# Com_Canbus.net
KiCad netlist of a schematic drawn in Altium Designer
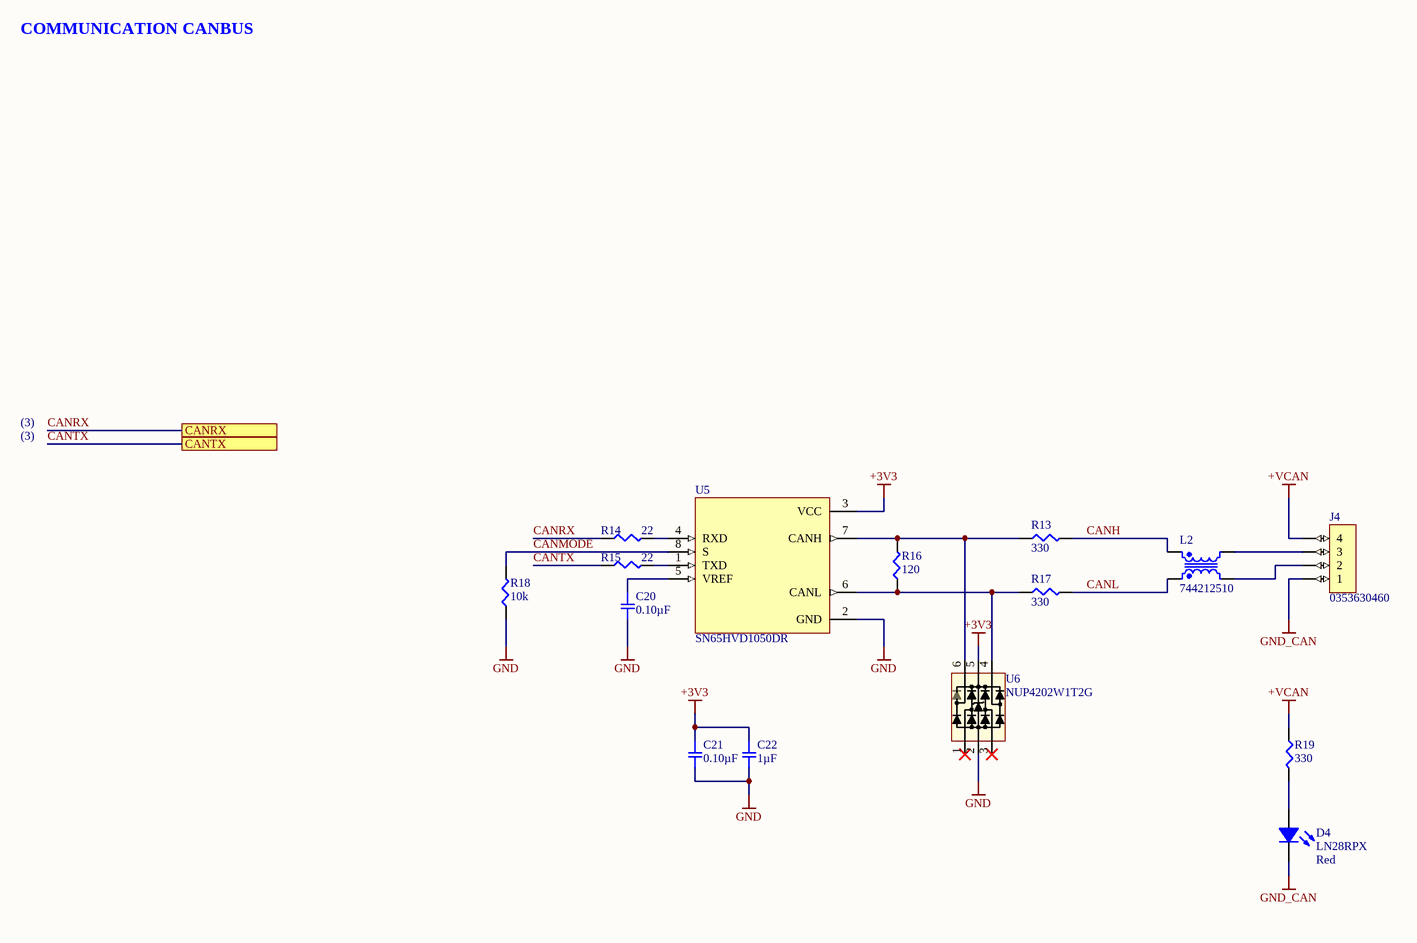
[diagram p0: Com_Canbus.SchDoc]

(export (version "E")
  (design (tool "Eeschema 10.0.6"))
  (components
    (comp (ref "C20")
      (value "0.10µF")
      (footprint "SMD-0603C")
      (description "CAP CER 0.1UF 50V X7R 0603")
      (fields
        (field (name "DIGI-KEY PART NUMBER") "490-5798-1-ND")
        (field (name "PART NUMBER") "GCJ188R71H104KA12D")
      )
      (libsource (lib "capacitor_murata_0603") (part "GCJ188R71H104KA12D"))
    )
    (comp (ref "C21")
      (value "0.10µF")
      (footprint "SMD-0603C")
      (description "CAP CER 0.1UF 50V X7R 0603")
      (fields
        (field (name "DIGI-KEY PART NUMBER") "490-5798-1-ND")
        (field (name "PART NUMBER") "GCJ188R71H104KA12D")
      )
      (libsource (lib "capacitor_murata_0603") (part "GCJ188R71H104KA12D"))
    )
    (comp (ref "C22")
      (value "1µF")
      (footprint "SMD-0603C")
      (description "CAP CER 1UF 16V X7R 0603")
      (fields
        (field (name "DIGI-KEY PART NUMBER") "490-5241-1-ND")
        (field (name "PART NUMBER") "GCM188R71C105KA64D")
      )
      (libsource (lib "capacitor_murata_0603") (part "GCM188R71C105KA64D"))
    )
    (comp (ref "D4")
      (value "LN28RPX")
      (footprint "Led-3mm-Red-h7")
      (description "LED RED DIFF 3MM ROUND T/H")
      (fields
        (field (name "MANUFACTURER") "Panasonic Electronic Components")
        (field (name "LENS COLOR") "Red")
      )
      (libsource (lib "Altium_Lib") (part "LED_RED__LN28RPX"))
    )
    (comp (ref "J4")
      (value "0353630460")
      (footprint "CONN_4_POS__0353630460")
      (description "CONN HEADER 4POS 2MM R/A TIN")
      (fields (field (name "MANUFACTURER") "Molex Connector Corporation"))
      (libsource (lib "Altium_Lib") (part "CONN_4_POS__0353630460"))
    )
    (comp (ref "L2")
      (value "744212510")
      (footprint "CM_6.50mm x 3.60mm")
      (description "Common Mode Filters / Chokes WE-SL1 SMD Ln Filter 2x51uH 300ohm")
      (fields (field (name "MANUFACTURER") "Wurth Electronics") (field (name "TOLERANCE") "50%"))
      (libsource (lib "Altium_Lib") (part "CM__744212510"))
    )
    (comp (ref "R13")
      (value "330")
      (footprint "SMD-0603-RES")
      (description "RES SMD 330 OHM 1% 1/10W 0603")
      (fields (field (name "PART NUMBER") "ERJ-3EKF3300V") (field (name "DIGI-KEY PART NUMBER") "P330HCT-ND"))
      (libsource (lib "Panasonic_ERJ_0603") (part "ERJ-3EKF3300V"))
    )
    (comp (ref "R14")
      (value "22")
      (footprint "SMD-0603-RES")
      (description "RES SMD 22 OHM 1% 1/10W 0603")
      (fields
        (field (name "PART NUMBER") "ERJ-3EKF22R0V")
        (field (name "DIGI-KEY PART NUMBER") "P22.0HCT-ND")
      )
      (libsource (lib "Panasonic_ERJ_0603") (part "ERJ-3EKF22R0V"))
    )
    (comp (ref "R15")
      (value "22")
      (footprint "SMD-0603-RES")
      (description "RES SMD 22 OHM 1% 1/10W 0603")
      (fields
        (field (name "PART NUMBER") "ERJ-3EKF22R0V")
        (field (name "DIGI-KEY PART NUMBER") "P22.0HCT-ND")
      )
      (libsource (lib "Panasonic_ERJ_0603") (part "ERJ-3EKF22R0V"))
    )
    (comp (ref "R16")
      (value "120")
      (footprint "SMD-0603-RES")
      (description "RES SMD 120 OHM 1% 1/10W 0603")
      (fields (field (name "PART NUMBER") "ERJ-3EKF1200V") (field (name "DIGI-KEY PART NUMBER") "P120HCT-ND"))
      (libsource (lib "Panasonic_ERJ_0603") (part "ERJ-3EKF1200V"))
    )
    (comp (ref "R17")
      (value "330")
      (footprint "SMD-0603-RES")
      (description "RES SMD 330 OHM 1% 1/10W 0603")
      (fields (field (name "PART NUMBER") "ERJ-3EKF3300V") (field (name "DIGI-KEY PART NUMBER") "P330HCT-ND"))
      (libsource (lib "Panasonic_ERJ_0603") (part "ERJ-3EKF3300V"))
    )
    (comp (ref "R18")
      (value "10k")
      (footprint "SMD-0603-RES")
      (description "RES SMD 10K OHM 1% 1/10W 0603")
      (fields
        (field (name "PART NUMBER") "ERJ-3EKF1002V")
        (field (name "DIGI-KEY PART NUMBER") "P10.0KHCT-ND")
      )
      (libsource (lib "Panasonic_ERJ_0603") (part "ERJ-3EKF1002V"))
    )
    (comp (ref "R19")
      (value "330")
      (footprint "SMD-0603-RES")
      (description "RES SMD 330 OHM 1% 1/10W 0603")
      (fields (field (name "PART NUMBER") "ERJ-3EKF3300V") (field (name "DIGI-KEY PART NUMBER") "P330HCT-ND"))
      (libsource (lib "Panasonic_ERJ_0603") (part "ERJ-3EKF3300V"))
    )
    (comp (ref "U5")
      (value "SN65HVD1050DR")
      (footprint "SOIC-8_L")
      (description "High-Speed CAN Transceiver with Silent Mode 8-SOIC -40 to 125")
      (fields (field (name "DIGI-KEY_PART_NUMBER") "296-26335-1-ND") (field (name "MF") "Texas Instruments"))
      (libsource (lib "Altium_Lib") (part "SN65HVD1050DR"))
    )
    (comp (ref "U6")
      (value "NUP4202W1T2G")
      (footprint "SOT-363")
      (description "TVS DIODE 5VWM 14.5VC SOT363")
      (fields (field (name "MANUFACTURER") "ON Semiconductor"))
      (libsource (lib "Altium_Lib") (part "NUP4202W1T2G"))
    )
  )
  (nets
    (net (code "1") (name "+3V3") (class "Default")
      (node (ref "C21") (pin "1") (pinfunction "1_1") (pintype "passive"))
      (node (ref "C22") (pin "1") (pinfunction "1_1") (pintype "passive"))
      (node (ref "U5") (pin "3") (pinfunction "VCC_3") (pintype "power_in"))
      (node (ref "U6") (pin "5") (pinfunction "5_5") (pintype "passive"))
    )
    (net (code "2") (name "+VCAN") (class "Default")
      (node (ref "J4") (pin "4") (pinfunction "4_4") (pintype "bidirectional"))
      (node (ref "R19") (pin "1") (pinfunction "1_1") (pintype "passive"))
    )
    (net (code "3") (name "/CANH") (class "Default")
      (node (ref "L2") (pin "3") (pinfunction "3_3") (pintype "passive"))
      (node (ref "R13") (pin "2") (pinfunction "2_2") (pintype "passive"))
    )
    (net (code "4") (name "/CANL") (class "Default")
      (node (ref "L2") (pin "1") (pinfunction "1_1") (pintype "passive"))
      (node (ref "R17") (pin "2") (pinfunction "2_2") (pintype "passive"))
    )
    (net (code "5") (name "/CANMODE") (class "Default")
      (node (ref "R18") (pin "2") (pinfunction "2_2") (pintype "passive"))
      (node (ref "U5") (pin "8") (pinfunction "S_8") (pintype "input"))
    )
    (net (code "6") (name "/CANRX") (class "Default")
      (node (ref "R14") (pin "1") (pinfunction "1_1") (pintype "passive"))
    )
    (net (code "7") (name "/CANTX") (class "Default")
      (node (ref "R15") (pin "1") (pinfunction "1_1") (pintype "passive"))
    )
    (net (code "8") (name "GND") (class "Default")
      (node (ref "C20") (pin "2") (pinfunction "2_2") (pintype "passive"))
      (node (ref "C21") (pin "2") (pinfunction "2_2") (pintype "passive"))
      (node (ref "C22") (pin "2") (pinfunction "2_2") (pintype "passive"))
      (node (ref "R18") (pin "1") (pinfunction "1_1") (pintype "passive"))
      (node (ref "U5") (pin "2") (pinfunction "GND_2") (pintype "power_in"))
      (node (ref "U6") (pin "2") (pinfunction "2_2") (pintype "passive"))
    )
    (net (code "9") (name "GND_CAN") (class "Default")
      (node (ref "D4") (pin "2") (pinfunction "K_2") (pintype "passive"))
      (node (ref "J4") (pin "1") (pinfunction "1_1") (pintype "bidirectional"))
    )
    (net (code "10") (name "Net-(D4-A)") (class "Default")
      (node (ref "D4") (pin "1") (pinfunction "A_1") (pintype "passive"))
      (node (ref "R19") (pin "2") (pinfunction "2_2") (pintype "passive"))
    )
    (net (code "11") (name "Net-(J4-Pad2)") (class "Default")
      (node (ref "J4") (pin "2") (pinfunction "2_2") (pintype "bidirectional"))
      (node (ref "L2") (pin "5") (pinfunction "5_5") (pintype "passive"))
    )
    (net (code "12") (name "Net-(J4-Pad3)") (class "Default")
      (node (ref "J4") (pin "3") (pinfunction "3_3") (pintype "bidirectional"))
      (node (ref "L2") (pin "4") (pinfunction "4_4") (pintype "passive"))
    )
    (net (code "13") (name "Net-(U5-CANH)") (class "Default")
      (node (ref "R13") (pin "1") (pinfunction "1_1") (pintype "passive"))
      (node (ref "R16") (pin "2") (pinfunction "2_2") (pintype "passive"))
      (node (ref "U5") (pin "7") (pinfunction "CANH_7") (pintype "output"))
      (node (ref "U6") (pin "6") (pinfunction "6_6") (pintype "passive"))
    )
    (net (code "14") (name "Net-(U5-CANL)") (class "Default")
      (node (ref "R16") (pin "1") (pinfunction "1_1") (pintype "passive"))
      (node (ref "R17") (pin "1") (pinfunction "1_1") (pintype "passive"))
      (node (ref "U5") (pin "6") (pinfunction "CANL_6") (pintype "output"))
      (node (ref "U6") (pin "4") (pinfunction "4_4") (pintype "passive"))
    )
    (net (code "15") (name "Net-(U5-RXD)") (class "Default")
      (node (ref "R14") (pin "2") (pinfunction "2_2") (pintype "passive"))
      (node (ref "U5") (pin "4") (pinfunction "RXD_4") (pintype "input"))
    )
    (net (code "16") (name "Net-(U5-TXD)") (class "Default")
      (node (ref "R15") (pin "2") (pinfunction "2_2") (pintype "passive"))
      (node (ref "U5") (pin "1") (pinfunction "TXD_1") (pintype "input"))
    )
    (net (code "17") (name "Net-(U5-VREF)") (class "Default")
      (node (ref "C20") (pin "1") (pinfunction "1_1") (pintype "passive"))
      (node (ref "U5") (pin "5") (pinfunction "VREF_5") (pintype "input"))
    )
    (net (code "18") (name "unconnected-(U6-Pad1)") (class "Default")
      (node (ref "U6") (pin "1") (pinfunction "1_1") (pintype "passive+no_connect"))
    )
    (net (code "19") (name "unconnected-(U6-Pad3)") (class "Default")
      (node (ref "U6") (pin "3") (pinfunction "3_3") (pintype "passive+no_connect"))
    )
  )
)
